# Source_VDDM.net
KiCad netlist of a schematic drawn in Altium Designer
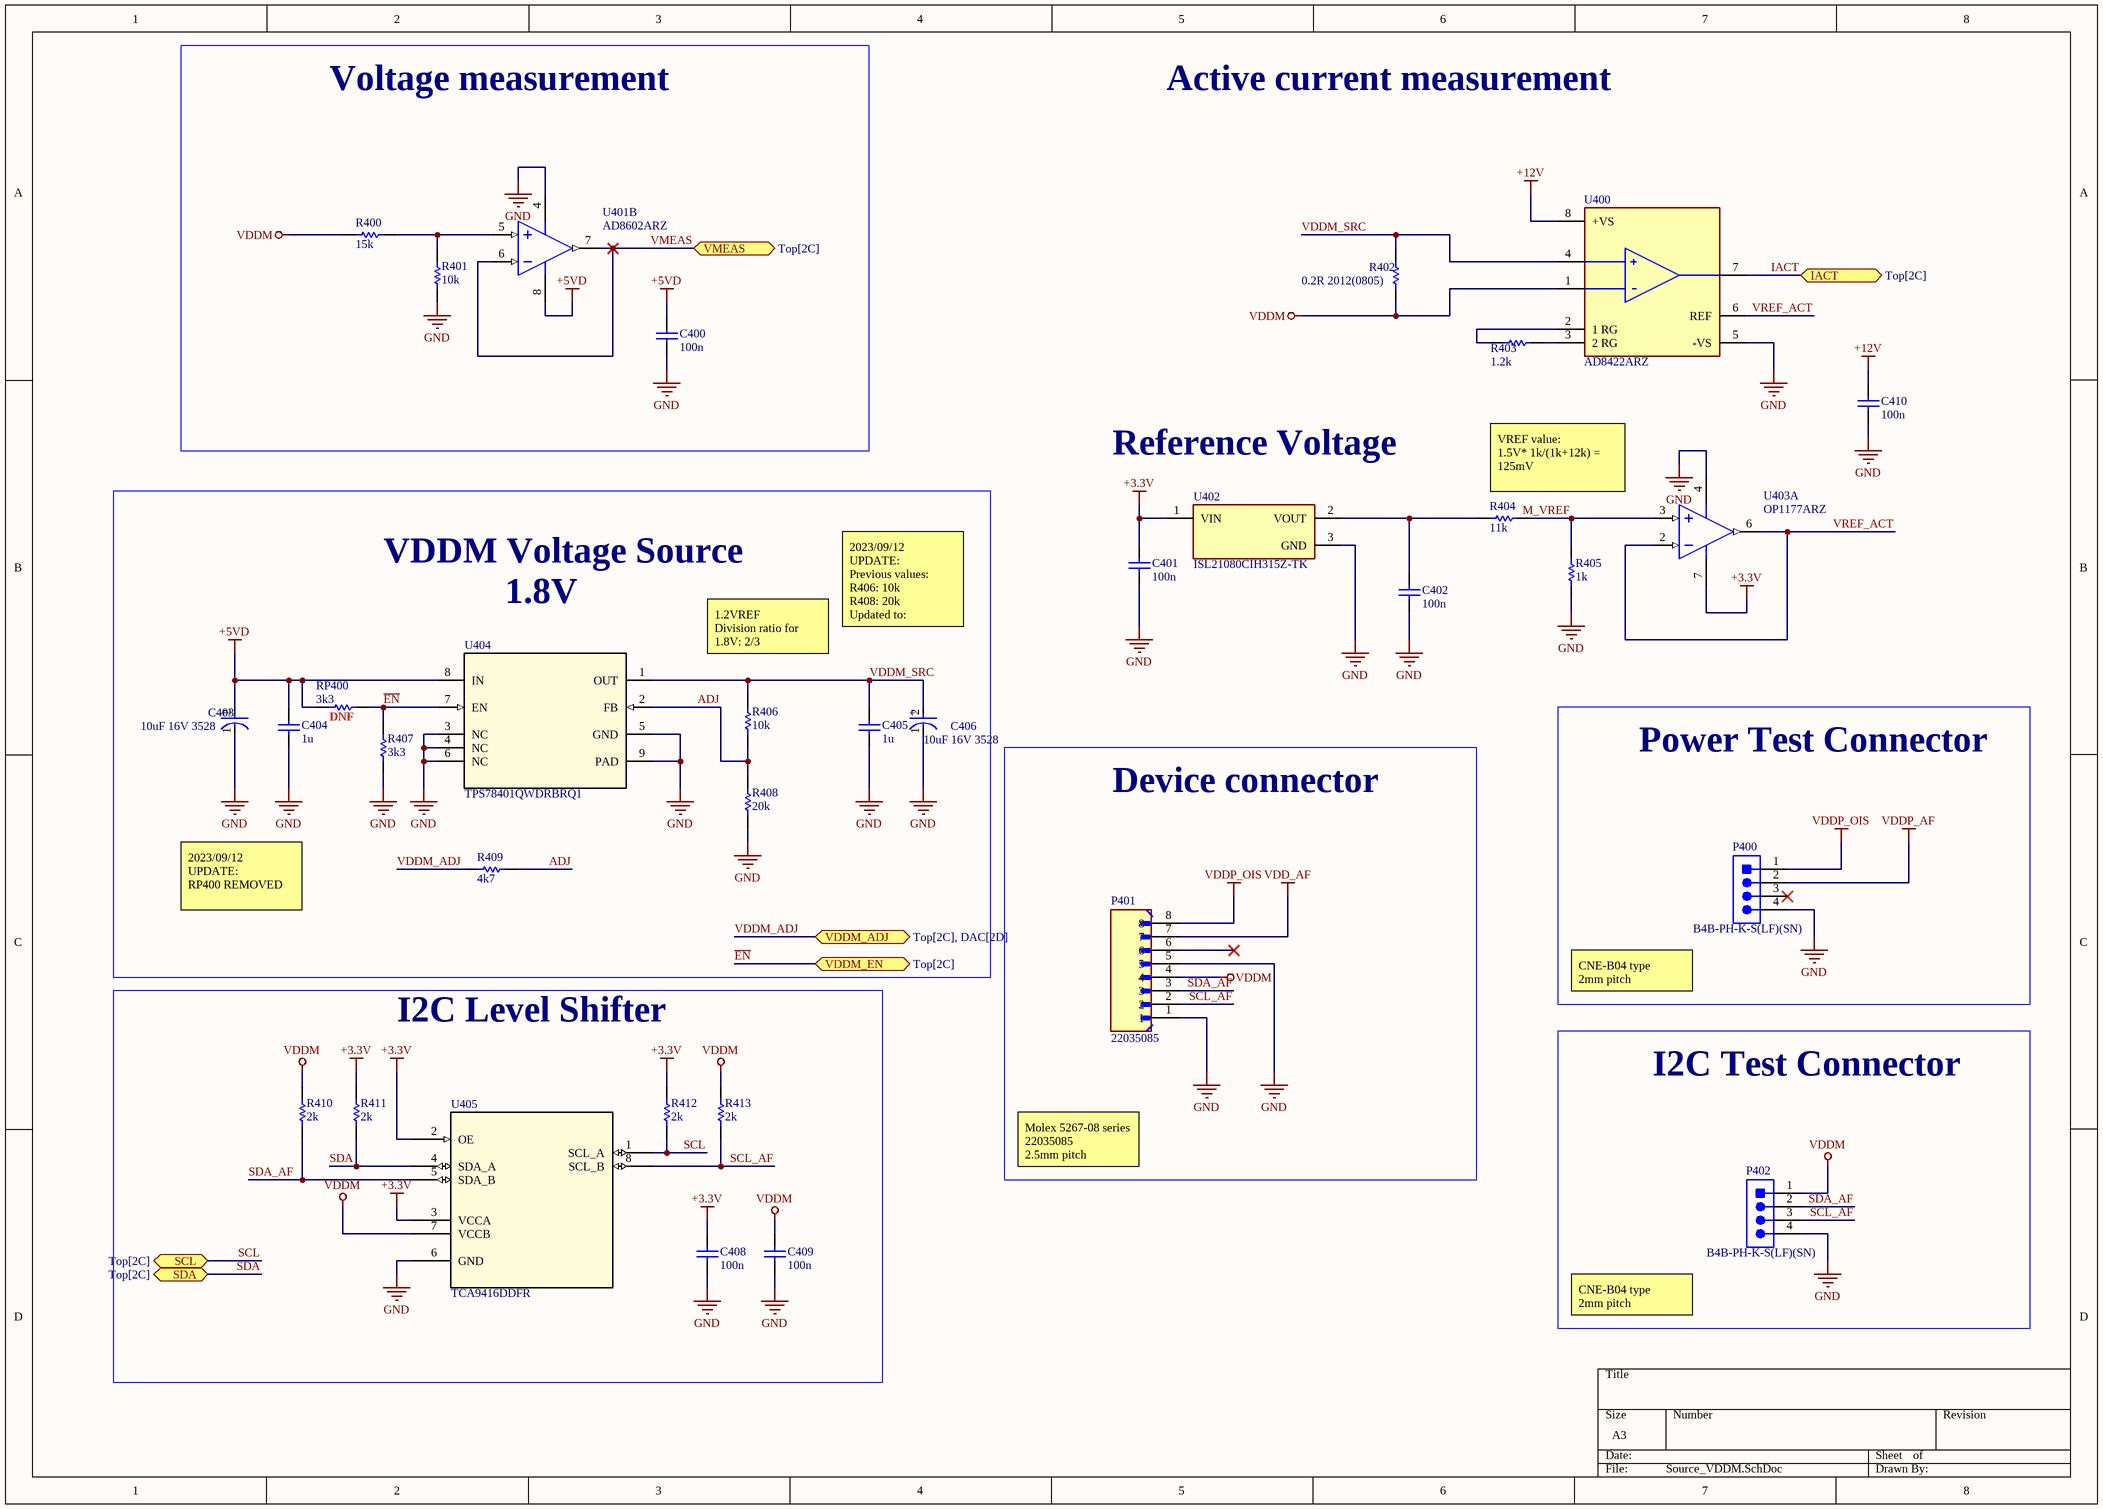
[diagram p0: Source_VDDM.SchDoc]

(export (version "E")
  (design (tool "Eeschema 10.0.6"))
  (components
    (comp (ref "C400")
      (value "100n")
      (footprint "SAMS-C0603-2_M")
      (description "Multi-layer Ceramic Capacitor, -55 to 125 degC, 2-Pin SMD (0603), RoHS, Tape and Reel")
      (fields (field (name "MANUFACTURER") "Samsung Electro-Mechanics"))
      (libsource (lib "Altium Content Vault") (part "CAP-NP-2"))
    )
    (comp (ref "C401")
      (value "100n")
      (footprint "SAMS-C0603-2_M")
      (description "Multi-layer Ceramic Capacitor, -55 to 125 degC, 2-Pin SMD (0603), RoHS, Tape and Reel")
      (fields (field (name "MANUFACTURER") "Samsung Electro-Mechanics"))
      (libsource (lib "Altium Content Vault") (part "CAP-NP-2"))
    )
    (comp (ref "C402")
      (value "100n")
      (footprint "SAMS-C0603-2_M")
      (description "Multi-layer Ceramic Capacitor, -55 to 125 degC, 2-Pin SMD (0603), RoHS, Tape and Reel")
      (fields (field (name "MANUFACTURER") "Samsung Electro-Mechanics"))
      (libsource (lib "Altium Content Vault") (part "CAP-NP-2"))
    )
    (comp (ref "C403")
      (value "10uF 16V 3528")
      (footprint "FP-T491B106K020AT-MFG")
      (description "CAP TANT 10UF 10% 20V 1411")
      (fields (field (name "TOLERANCE") "10%") (field (name "VOLTAGE") "20V"))
      (libsource (lib "Altium Content Vault") (part "a00bbbee19879c290e62620ae7e47b1"))
    )
    (comp (ref "C404")
      (value "1u")
      (footprint "CAPC2013X70X45NL10T25")
      (fields (field (name "PART NUMBER") "GRM216R61E105KA12D") (field (name "MANUFACTURER") "Murata"))
      (libsource (lib "Altium Content Vault") (part "CAP"))
    )
    (comp (ref "C405")
      (value "1u")
      (footprint "CAPC2013X70X45NL10T25")
      (fields (field (name "PART NUMBER") "GRM216R61E105KA12D") (field (name "MANUFACTURER") "Murata"))
      (libsource (lib "Altium Content Vault") (part "CAP"))
    )
    (comp (ref "C406")
      (value "10uF 16V 3528")
      (footprint "FP-T491B106K020AT-MFG")
      (description "CAP TANT 10UF 10% 20V 1411")
      (fields (field (name "TOLERANCE") "10%") (field (name "VOLTAGE") "20V"))
      (libsource (lib "Altium Content Vault") (part "a00bbbee19879c290e62620ae7e47b1"))
    )
    (comp (ref "C408")
      (value "100n")
      (footprint "SAMS-C0603-2_M")
      (description "Multi-layer Ceramic Capacitor, -55 to 125 degC, 2-Pin SMD (0603), RoHS, Tape and Reel")
      (fields (field (name "MANUFACTURER") "Samsung Electro-Mechanics"))
      (libsource (lib "Altium Content Vault") (part "CAP-NP-2"))
    )
    (comp (ref "C409")
      (value "100n")
      (footprint "SAMS-C0603-2_M")
      (description "Multi-layer Ceramic Capacitor, -55 to 125 degC, 2-Pin SMD (0603), RoHS, Tape and Reel")
      (fields (field (name "MANUFACTURER") "Samsung Electro-Mechanics"))
      (libsource (lib "Altium Content Vault") (part "CAP-NP-2"))
    )
    (comp (ref "C410")
      (value "100n")
      (footprint "SAMS-C0603-2_M")
      (description "Multi-layer Ceramic Capacitor, -55 to 125 degC, 2-Pin SMD (0603), RoHS, Tape and Reel")
      (fields (field (name "MANUFACTURER") "Samsung Electro-Mechanics"))
      (libsource (lib "Altium Content Vault") (part "CAP-NP-2"))
    )
    (comp (ref "P400")
      (value "B4B-PH-K-S(LF)(SN)")
      (footprint "JST-B4B-PH-K-S_V")
      (fields (field (name "MANUFACTURER") "JST"))
      (libsource (lib "Altium Content Vault") (part "CN-1P-M-R4"))
    )
    (comp (ref "P401")
      (value "22035085")
      (footprint "MOLEX_22035085")
      (libsource (lib "22035085") (part "22035085"))
    )
    (comp (ref "P402")
      (value "B4B-PH-K-S(LF)(SN)")
      (footprint "JST-B4B-PH-K-S_V")
      (fields (field (name "MANUFACTURER") "JST"))
      (libsource (lib "Altium Content Vault") (part "CN-1P-M-R4"))
    )
    (comp (ref "R400")
      (value "15k")
      (footprint "RESC1608X55X30ML15T15")
      (fields (field (name "PART NUMBER") "ERJ-3EKF3602V") (field (name "MANUFACTURER") "Panasonic"))
      (libsource (lib "Altium Content Vault") (part "RES"))
    )
    (comp (ref "R401")
      (value "10k")
      (footprint "RESC1608X55X30ML15T15")
      (fields (field (name "PART NUMBER") "ERJ-3GEYJ303V") (field (name "MANUFACTURER") "Panasonic"))
      (libsource (lib "Altium Content Vault") (part "RES"))
    )
    (comp (ref "R402")
      (value "0.2R 2012(0805)")
      (footprint "RESC2013X46X38ML25T25")
      (fields (field (name "PART NUMBER") "WSL0805R2000FEA") (field (name "MANUFACTURER") "Vishay Dale"))
      (libsource (lib "Altium Content Vault") (part "RES"))
    )
    (comp (ref "R403")
      (value "1.2k")
      (footprint "RESC1609X55X30ML15T15")
      (description "Chip Resistor, 1.2 KOhm, +/- 1%, 0.1 W, -55 to 155 degC, 0603 (1608 Metric), RoHS, Tape and Reel")
      (fields (field (name "MANUFACTURER") "Panasonic") (field (name "TOLERANCE") "1%"))
      (libsource (lib "Altium Content Vault") (part "RES-2"))
    )
    (comp (ref "R404")
      (value "11k")
      (footprint "RESC1608X55X30ML15T15")
      (fields (field (name "PART NUMBER") "ERJ-3EKF1102V") (field (name "MANUFACTURER") "Panasonic"))
      (libsource (lib "Altium Content Vault") (part "RES"))
    )
    (comp (ref "R405")
      (value "1k")
      (footprint "RESC1608X55X30ML15T15")
      (fields (field (name "PART NUMBER") "ERJ-3EKF1001V") (field (name "MANUFACTURER") "Panasonic"))
      (libsource (lib "Altium Content Vault") (part "RES"))
    )
    (comp (ref "R406")
      (value "10k")
      (footprint "RESC1609X55X30ML15T15")
      (description "Chip Resistor, 10 KOhm, +/- 1%, 0.1 W, -55 to 155 degC, 0603 (1608 Metric), RoHS, Tape and Reel")
      (fields (field (name "TOLERANCE") "1%") (field (name "MANUFACTURER") "Panasonic"))
      (libsource (lib "Altium Content Vault") (part "RES-2"))
    )
    (comp (ref "R407")
      (value "3k3")
      (footprint "RESC1609X55X30ML15T15")
      (description "Chip Resistors, 3.3 KOhm, +/- 1%, 0.1 W, 0603 (1608 Metric), -55 to 155 degC, RoHS, Tape and Reel")
      (fields (field (name "MANUFACTURER") "Panasonic") (field (name "TOLERANCE") "1%"))
      (libsource (lib "Altium Content Vault") (part "RES-2"))
    )
    (comp (ref "R408")
      (value "20k")
      (footprint "RESC1609X55X30ML15T15")
      (description "Chip Resistor, 10 KOhm, +/- 1%, 0.1 W, -55 to 155 degC, 0603 (1608 Metric), RoHS, Tape and Reel")
      (fields (field (name "TOLERANCE") "1%") (field (name "MANUFACTURER") "Panasonic"))
      (libsource (lib "Altium Content Vault") (part "RES-2"))
    )
    (comp (ref "R409")
      (value "4k7")
      (footprint "RESC1608X55X30ML15T15")
      (fields (field (name "TOLERANCE") "5%"))
      (libsource (lib "Altium Content Vault") (part "RES-2"))
    )
    (comp (ref "R410")
      (value "2k")
      (footprint "RESC1608X55X30ML15T15")
      (fields (field (name "PART NUMBER") "ERJ-3EKF2001V") (field (name "MANUFACTURER") "Panasonic"))
      (libsource (lib "Altium Content Vault") (part "RES"))
    )
    (comp (ref "R411")
      (value "2k")
      (footprint "RESC1608X55X30ML15T15")
      (fields (field (name "PART NUMBER") "ERJ-3EKF2001V") (field (name "MANUFACTURER") "Panasonic"))
      (libsource (lib "Altium Content Vault") (part "RES"))
    )
    (comp (ref "R412")
      (value "2k")
      (footprint "RESC1608X55X30ML15T15")
      (fields (field (name "PART NUMBER") "ERJ-3EKF2001V") (field (name "MANUFACTURER") "Panasonic"))
      (libsource (lib "Altium Content Vault") (part "RES"))
    )
    (comp (ref "R413")
      (value "2k")
      (footprint "RESC1608X55X30ML15T15")
      (fields (field (name "PART NUMBER") "ERJ-3EKF2001V") (field (name "MANUFACTURER") "Panasonic"))
      (libsource (lib "Altium Content Vault") (part "RES"))
    )
    (comp (ref "RP400")
      (value "3k3")
      (footprint "RESC1609X55X30ML15T15")
      (description "Chip Resistors, 3.3 KOhm, +/- 1%, 0.1 W, 0603 (1608 Metric), -55 to 155 degC, RoHS, Tape and Reel")
      (fields (field (name "MANUFACTURER") "Panasonic") (field (name "TOLERANCE") "1%"))
      (libsource (lib "Altium Content Vault") (part "RES-2"))
    )
    (comp (ref "U400")
      (value "AD8422ARZ")
      (footprint "FP-R-8-IPC_A")
      (description "IC INST AMP 1 CIRCUIT 8SOIC")
      (libsource (lib "Altium Content Vault") (part "c8ce1a14eba5bbcc74e575812f36567"))
    )
    (comp (ref "U401")
      (value "AD8602ARZ")
      (footprint "ADI-R-8_N")
      (fields (field (name "GENERIC PART NUMBER") "AD8602") (field (name "MANUFACTURER") "Analog Devices"))
      (libsource (lib "Altium Content Vault") (part "ADI-OP29X-R-8"))
    )
    (comp (ref "U402")
      (value "ISL21080CIH315Z-TK")
      (footprint "FP-P3_064A-IPC_A")
      (description "IC VREF SERIES 0.5% SOT23-3")
      (libsource (lib "Altium Content Vault") (part "962e5ce8f08f2276f18e857990e14fe"))
    )
    (comp (ref "U403")
      (value "OP1177ARZ")
      (footprint "ADI-R-8_M")
      (fields (field (name "MANUFACTURER") "Analog Devices") (field (name "GENERIC PART NUMBER") "OP1177"))
      (libsource (lib "Altium Content Vault") (part "ADI-AD_ADA_OPXXXX-X-8"))
    )
    (comp (ref "U404")
      (value "TPS78401QWDRBRQ1")
      (footprint "DRB0008J-IPC_A")
      (description "No Description Available")
      (fields (field (name "COPYRIGHT") "Copyright (C) 2022 Ultra Librarian. All rights reserved."))
      (libsource (lib "TPS78401QWDRBRQ1") (part "TPS78401QWDRBRQ1"))
    )
    (comp (ref "U405")
      (value "TCA9416DDFR")
      (footprint "SOT_16DDFR_TEX")
      (description "No Description Available")
      (fields (field (name "COPYRIGHT") "Copyright (C) 2022 Ultra Librarian. All rights reserved."))
      (libsource (lib "TCA9416DDFR") (part "TCA9416DDFR"))
    )
  )
  (nets
    (net (code "1") (name "+3.3V") (class "Default")
      (node (ref "C401") (pin "2") (pinfunction "2_2") (pintype "passive"))
      (node (ref "C408") (pin "2") (pinfunction "2_2") (pintype "passive"))
      (node (ref "R411") (pin "2") (pinfunction "2_2") (pintype "passive"))
      (node (ref "R412") (pin "2") (pinfunction "2_2") (pintype "passive"))
      (node (ref "U402") (pin "1") (pinfunction "VIN_1") (pintype "power_in"))
      (node (ref "U403") (pin "7") (pinfunction "+V_7") (pintype "power_in"))
      (node (ref "U405") (pin "2") (pinfunction "OE_2") (pintype "input"))
      (node (ref "U405") (pin "3") (pinfunction "VCCA_3") (pintype "power_in"))
    )
    (net (code "2") (name "+5VD") (class "Default")
      (node (ref "C400") (pin "2") (pinfunction "2_2") (pintype "passive"))
      (node (ref "C403") (pin "2") (pinfunction "A_2") (pintype "passive"))
      (node (ref "C404") (pin "2") (pinfunction "2_2") (pintype "passive"))
      (node (ref "RP400") (pin "2") (pinfunction "2_2") (pintype "passive"))
      (node (ref "U401") (pin "8") (pinfunction "+V_8") (pintype "power_in"))
      (node (ref "U404") (pin "8") (pinfunction "IN_8") (pintype "power_in"))
    )
    (net (code "3") (name "+12V") (class "Default")
      (node (ref "C410") (pin "2") (pinfunction "2_2") (pintype "passive"))
      (node (ref "U400") (pin "8") (pinfunction "+VS_8") (pintype "power_in"))
    )
    (net (code "4") (name "/ADJ") (class "Default")
      (node (ref "R406") (pin "1") (pinfunction "1_1") (pintype "passive"))
      (node (ref "R408") (pin "2") (pinfunction "2_2") (pintype "passive"))
      (node (ref "R409") (pin "2") (pinfunction "2_2") (pintype "passive"))
      (node (ref "U404") (pin "2") (pinfunction "FB_2") (pintype "input"))
    )
    (net (code "5") (name "/IACT") (class "Default")
      (node (ref "U400") (pin "7") (pinfunction "VOUT_7") (pintype "passive"))
    )
    (net (code "6") (name "/M_VREF") (class "Default")
      (node (ref "R404") (pin "1") (pinfunction "1_1") (pintype "passive"))
      (node (ref "R405") (pin "2") (pinfunction "2_2") (pintype "passive"))
      (node (ref "U403") (pin "3") (pinfunction "+IN_3") (pintype "input"))
    )
    (net (code "7") (name "/SCL") (class "Default")
      (node (ref "R412") (pin "1") (pinfunction "1_1") (pintype "passive"))
      (node (ref "U405") (pin "1") (pinfunction "SCL_A_1") (pintype "bidirectional"))
    )
    (net (code "8") (name "/SCL_AF") (class "Default")
      (node (ref "P401") (pin "2") (pinfunction "2_2") (pintype "passive"))
      (node (ref "P402") (pin "3") (pinfunction "3_3") (pintype "passive"))
      (node (ref "R413") (pin "1") (pinfunction "1_1") (pintype "passive"))
      (node (ref "U405") (pin "8") (pinfunction "SCL_B_8") (pintype "bidirectional"))
    )
    (net (code "9") (name "/SDA") (class "Default")
      (node (ref "R411") (pin "1") (pinfunction "1_1") (pintype "passive"))
      (node (ref "U405") (pin "4") (pinfunction "SDA_A_4") (pintype "bidirectional"))
    )
    (net (code "10") (name "/SDA_AF") (class "Default")
      (node (ref "P401") (pin "3") (pinfunction "3_3") (pintype "passive"))
      (node (ref "P402") (pin "2") (pinfunction "2_2") (pintype "passive"))
      (node (ref "R410") (pin "1") (pinfunction "1_1") (pintype "passive"))
      (node (ref "U405") (pin "5") (pinfunction "SDA_B_5") (pintype "bidirectional"))
    )
    (net (code "11") (name "/VDDM_ADJ") (class "Default")
      (node (ref "R409") (pin "1") (pinfunction "1_1") (pintype "passive"))
    )
    (net (code "12") (name "/VDDM_SRC") (class "Default")
      (node (ref "C405") (pin "2") (pinfunction "2_2") (pintype "passive"))
      (node (ref "C406") (pin "2") (pinfunction "A_2") (pintype "passive"))
      (node (ref "R402") (pin "2") (pinfunction "2_2") (pintype "passive"))
      (node (ref "R406") (pin "2") (pinfunction "2_2") (pintype "passive"))
      (node (ref "U400") (pin "4") (pinfunction "+IN_4") (pintype "tri_state"))
      (node (ref "U404") (pin "1") (pinfunction "OUT_1") (pintype "power_in"))
    )
    (net (code "13") (name "/VMEAS") (class "Default")
      (node (ref "U401") (pin "6") (pinfunction "-IN_B_6") (pintype "input"))
      (node (ref "U401") (pin "7") (pinfunction "OUT_B_7") (pintype "output"))
    )
    (net (code "14") (name "/VREF_ACT") (class "Default")
      (node (ref "U400") (pin "6") (pinfunction "REF_6") (pintype "passive"))
      (node (ref "U403") (pin "2") (pinfunction "-IN_2") (pintype "input"))
      (node (ref "U403") (pin "6") (pinfunction "OUT_6") (pintype "output"))
    )
    (net (code "15") (name "/~{EN}") (class "Default")
      (node (ref "R407") (pin "2") (pinfunction "2_2") (pintype "passive"))
      (node (ref "RP400") (pin "1") (pinfunction "1_1") (pintype "passive"))
      (node (ref "U404") (pin "7") (pinfunction "EN_7") (pintype "input"))
    )
    (net (code "16") (name "GND") (class "Default")
      (node (ref "C400") (pin "1") (pinfunction "1_1") (pintype "passive"))
      (node (ref "C401") (pin "1") (pinfunction "1_1") (pintype "passive"))
      (node (ref "C402") (pin "1") (pinfunction "1_1") (pintype "passive"))
      (node (ref "C403") (pin "1") (pinfunction "C_1") (pintype "passive"))
      (node (ref "C404") (pin "1") (pinfunction "1_1") (pintype "passive"))
      (node (ref "C405") (pin "1") (pinfunction "1_1") (pintype "passive"))
      (node (ref "C406") (pin "1") (pinfunction "C_1") (pintype "passive"))
      (node (ref "C408") (pin "1") (pinfunction "1_1") (pintype "passive"))
      (node (ref "C409") (pin "1") (pinfunction "1_1") (pintype "passive"))
      (node (ref "C410") (pin "1") (pinfunction "1_1") (pintype "passive"))
      (node (ref "P400") (pin "4") (pinfunction "4_4") (pintype "passive"))
      (node (ref "P401") (pin "1") (pinfunction "1_1") (pintype "passive"))
      (node (ref "P401") (pin "5") (pinfunction "5_5") (pintype "passive"))
      (node (ref "P402") (pin "4") (pinfunction "4_4") (pintype "passive"))
      (node (ref "R401") (pin "1") (pinfunction "1_1") (pintype "passive"))
      (node (ref "R405") (pin "1") (pinfunction "1_1") (pintype "passive"))
      (node (ref "R407") (pin "1") (pinfunction "1_1") (pintype "passive"))
      (node (ref "R408") (pin "1") (pinfunction "1_1") (pintype "passive"))
      (node (ref "U400") (pin "5") (pinfunction "-VS_5") (pintype "power_in"))
      (node (ref "U401") (pin "4") (pinfunction "-V_4") (pintype "power_in"))
      (node (ref "U402") (pin "3") (pinfunction "GND_3") (pintype "power_in"))
      (node (ref "U403") (pin "4") (pinfunction "-V_4") (pintype "power_in"))
      (node (ref "U404") (pin "3") (pinfunction "NC_3") (pintype "passive"))
      (node (ref "U404") (pin "4") (pinfunction "NC_4") (pintype "passive"))
      (node (ref "U404") (pin "5") (pinfunction "GND_5") (pintype "power_in"))
      (node (ref "U404") (pin "6") (pinfunction "NC_6") (pintype "passive"))
      (node (ref "U404") (pin "9") (pinfunction "PAD_9") (pintype "passive"))
      (node (ref "U405") (pin "6") (pinfunction "GND_6") (pintype "power_in"))
    )
    (net (code "17") (name "Net-(U400-1_RG)") (class "Default")
      (node (ref "R403") (pin "1") (pinfunction "1_1") (pintype "passive"))
      (node (ref "U400") (pin "2") (pinfunction "1_RG_2") (pintype "passive"))
    )
    (net (code "18") (name "Net-(U400-2_RG)") (class "Default")
      (node (ref "R403") (pin "2") (pinfunction "2_2") (pintype "passive"))
      (node (ref "U400") (pin "3") (pinfunction "2_RG_3") (pintype "passive"))
    )
    (net (code "19") (name "Net-(U401B-+IN_B)") (class "Default")
      (node (ref "R400") (pin "2") (pinfunction "2_2") (pintype "passive"))
      (node (ref "R401") (pin "2") (pinfunction "2_2") (pintype "passive"))
      (node (ref "U401") (pin "5") (pinfunction "+IN_B_5") (pintype "input"))
    )
    (net (code "20") (name "Net-(U402-VOUT)") (class "Default")
      (node (ref "C402") (pin "2") (pinfunction "2_2") (pintype "passive"))
      (node (ref "R404") (pin "2") (pinfunction "2_2") (pintype "passive"))
      (node (ref "U402") (pin "2") (pinfunction "VOUT_2") (pintype "power_in"))
    )
    (net (code "21") (name "VDDM") (class "Default")
      (node (ref "C409") (pin "2") (pinfunction "2_2") (pintype "passive"))
      (node (ref "P401") (pin "4") (pinfunction "4_4") (pintype "passive"))
      (node (ref "P402") (pin "1") (pinfunction "1_1") (pintype "passive"))
      (node (ref "R400") (pin "1") (pinfunction "1_1") (pintype "passive"))
      (node (ref "R402") (pin "1") (pinfunction "1_1") (pintype "passive"))
      (node (ref "R410") (pin "2") (pinfunction "2_2") (pintype "passive"))
      (node (ref "R413") (pin "2") (pinfunction "2_2") (pintype "passive"))
      (node (ref "U400") (pin "1") (pinfunction "-IN_1") (pintype "tri_state"))
      (node (ref "U405") (pin "7") (pinfunction "VCCB_7") (pintype "power_in"))
    )
    (net (code "22") (name "VDDP_AF") (class "Default")
      (node (ref "P400") (pin "2") (pinfunction "2_2") (pintype "passive"))
    )
    (net (code "23") (name "VDDP_OIS") (class "Default")
      (node (ref "P400") (pin "1") (pinfunction "1_1") (pintype "passive"))
      (node (ref "P401") (pin "8") (pinfunction "8_8") (pintype "passive"))
    )
    (net (code "24") (name "VDD_AF") (class "Default")
      (node (ref "P401") (pin "7") (pinfunction "7_7") (pintype "passive"))
    )
    (net (code "25") (name "unconnected-(P400-Pad3)") (class "Default")
      (node (ref "P400") (pin "3") (pinfunction "3_3") (pintype "passive+no_connect"))
    )
    (net (code "26") (name "unconnected-(P401-Pad6)") (class "Default")
      (node (ref "P401") (pin "6") (pinfunction "6_6") (pintype "passive+no_connect"))
    )
  )
)
